# FPGA3.net
KiCad netlist of a schematic drawn in Altium Designer
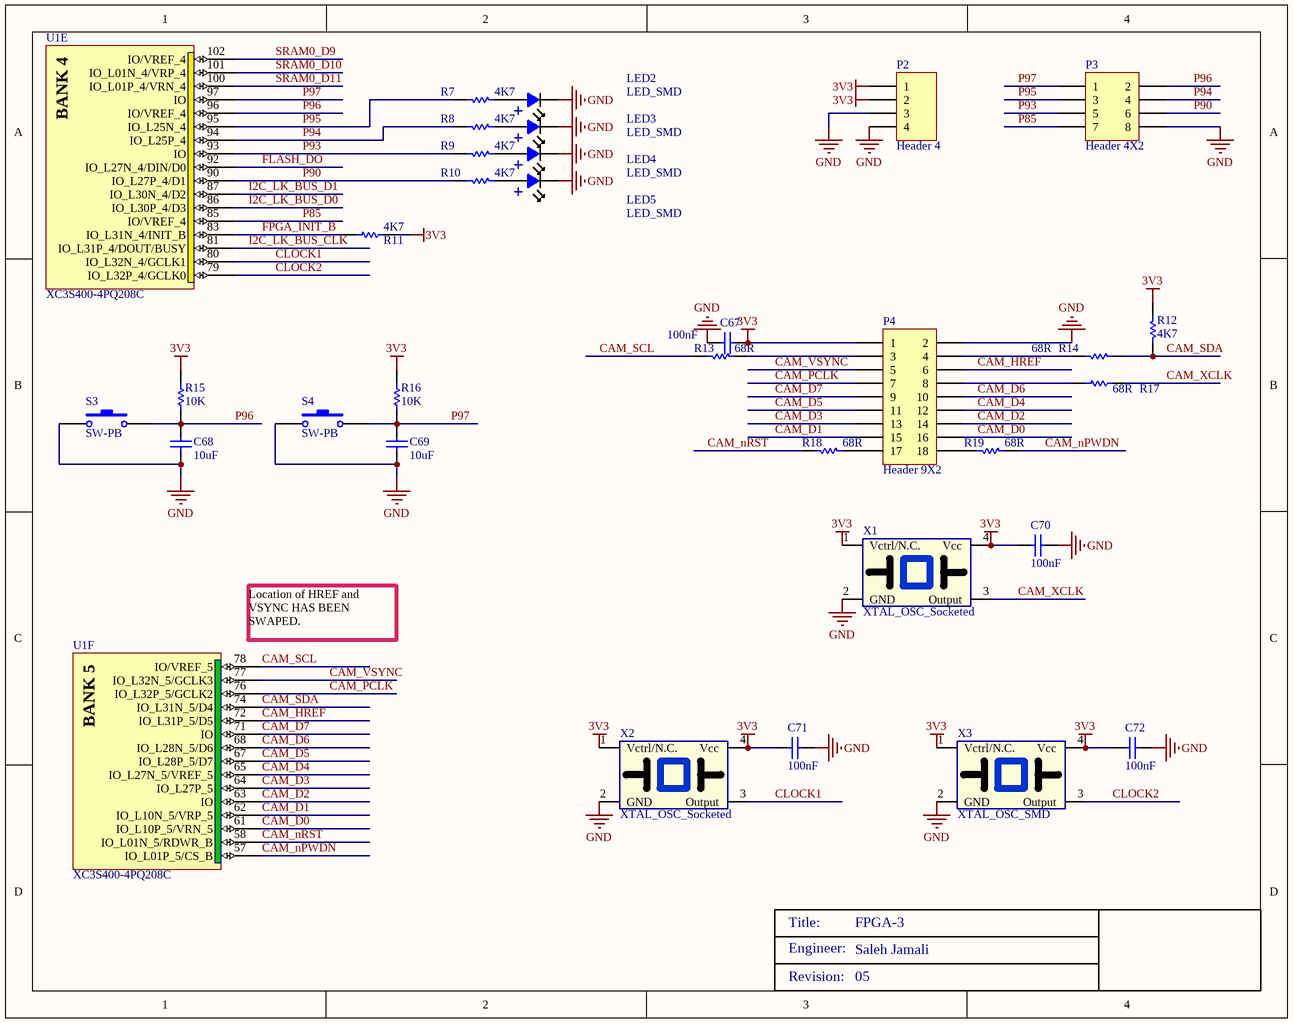
[diagram p0: FPGA3.SchDoc]

(export (version "E")
  (design (tool "Eeschema 10.0.6"))
  (components
    (comp (ref "C67")
      (value "100nF")
      (footprint "0805")
      (description "Ceramic Chip Capacitor - Standard")
      (fields (field (name "Comment") "C0805") (field (name "PUBLISHER") "Altium Limited"))
      (libsource (lib "KEMET Chip Capacitor") (part "C0805"))
    )
    (comp (ref "C68")
      (value "10uF")
      (footprint "0805")
      (description "Ceramic Chip Capacitor - Standard")
      (fields (field (name "Comment") "C0805") (field (name "PUBLISHER") "Altium Limited"))
      (libsource (lib "KEMET Chip Capacitor") (part "C0805"))
    )
    (comp (ref "C69")
      (value "10uF")
      (footprint "0805")
      (description "Ceramic Chip Capacitor - Standard")
      (fields (field (name "Comment") "C0805") (field (name "PUBLISHER") "Altium Limited"))
      (libsource (lib "KEMET Chip Capacitor") (part "C0805"))
    )
    (comp (ref "C70")
      (value "100nF")
      (footprint "0805")
      (description "Ceramic Chip Capacitor - Standard")
      (fields (field (name "Comment") "C0805") (field (name "PUBLISHER") "Altium Limited"))
      (libsource (lib "KEMET Chip Capacitor") (part "C0805"))
    )
    (comp (ref "C71")
      (value "100nF")
      (footprint "0805")
      (description "Ceramic Chip Capacitor - Standard")
      (fields (field (name "Comment") "C0805") (field (name "PUBLISHER") "Altium Limited"))
      (libsource (lib "KEMET Chip Capacitor") (part "C0805"))
    )
    (comp (ref "C72")
      (value "100nF")
      (footprint "0805")
      (description "Ceramic Chip Capacitor - Standard")
      (fields (field (name "Comment") "C0805") (field (name "PUBLISHER") "Altium Limited"))
      (libsource (lib "KEMET Chip Capacitor") (part "C0805"))
    )
    (comp (ref "LED2") (value "LED_SMD") (footprint "LED_805") (libsource (lib "LED_PRJCT") (part "LED_SMD")))
    (comp (ref "LED3") (value "LED_SMD") (footprint "LED_805") (libsource (lib "LED_PRJCT") (part "LED_SMD")))
    (comp (ref "LED4") (value "LED_SMD") (footprint "LED_805") (libsource (lib "LED_PRJCT") (part "LED_SMD")))
    (comp (ref "LED5") (value "LED_SMD") (footprint "LED_805") (libsource (lib "LED_PRJCT") (part "LED_SMD")))
    (comp (ref "P2")
      (value "Header 4")
      (footprint "HDR1X4")
      (description "Header, 4-Pin")
      (fields (field (name "PUBLISHER") "Altium Limited"))
      (libsource (lib "Miscellaneous Connectors") (part "Header 4"))
    )
    (comp (ref "P3")
      (value "Header 4X2")
      (footprint "HDR2X4")
      (description "Header, 4-Pin, Dual row")
      (fields (field (name "PUBLISHER") "Altium Limited"))
      (libsource (lib "Miscellaneous Connectors") (part "Header 4X2"))
    )
    (comp (ref "P4")
      (value "Header 9X2")
      (footprint "HDR2X9")
      (description "Header, 9-Pin, Dual row")
      (fields (field (name "PUBLISHER") "Altium Limited"))
      (libsource (lib "Miscellaneous Connectors") (part "Header 9X2"))
    )
    (comp (ref "R7")
      (value "4K7")
      (footprint "ERA-0805")
      (fields (field (name "PUBLISHER") "Altium Limited"))
      (libsource (lib "Panasonic Resistor") (part "ERA6Y"))
    )
    (comp (ref "R8")
      (value "4K7")
      (footprint "ERA-0805")
      (fields (field (name "PUBLISHER") "Altium Limited"))
      (libsource (lib "Panasonic Resistor") (part "ERA6Y"))
    )
    (comp (ref "R9")
      (value "4K7")
      (footprint "ERA-0805")
      (fields (field (name "PUBLISHER") "Altium Limited"))
      (libsource (lib "Panasonic Resistor") (part "ERA6Y"))
    )
    (comp (ref "R10")
      (value "4K7")
      (footprint "ERA-0805")
      (fields (field (name "PUBLISHER") "Altium Limited"))
      (libsource (lib "Panasonic Resistor") (part "ERA6Y"))
    )
    (comp (ref "R11")
      (value "4K7")
      (footprint "ERA-0805")
      (fields (field (name "PUBLISHER") "Altium Limited"))
      (libsource (lib "Panasonic Resistor") (part "ERA6Y"))
    )
    (comp (ref "R12")
      (value "4K7")
      (footprint "ERA-0805")
      (fields (field (name "PUBLISHER") "Altium Limited"))
      (libsource (lib "Panasonic Resistor") (part "ERA6Y"))
    )
    (comp (ref "R13")
      (value "68R")
      (footprint "ERA-0805")
      (fields (field (name "PUBLISHER") "Altium Limited"))
      (libsource (lib "Panasonic Resistor") (part "ERA6Y"))
    )
    (comp (ref "R14")
      (value "68R")
      (footprint "ERA-0805")
      (fields (field (name "PUBLISHER") "Altium Limited"))
      (libsource (lib "Panasonic Resistor") (part "ERA6Y"))
    )
    (comp (ref "R15")
      (value "10K")
      (footprint "ERA-0805")
      (fields (field (name "PUBLISHER") "Altium Limited"))
      (libsource (lib "Panasonic Resistor") (part "ERA6Y"))
    )
    (comp (ref "R16")
      (value "10K")
      (footprint "ERA-0805")
      (fields (field (name "PUBLISHER") "Altium Limited"))
      (libsource (lib "Panasonic Resistor") (part "ERA6Y"))
    )
    (comp (ref "R17")
      (value "68R")
      (footprint "ERA-0805")
      (fields (field (name "PUBLISHER") "Altium Limited"))
      (libsource (lib "Panasonic Resistor") (part "ERA6Y"))
    )
    (comp (ref "R18")
      (value "68R")
      (footprint "ERA-0805")
      (fields (field (name "PUBLISHER") "Altium Limited"))
      (libsource (lib "Panasonic Resistor") (part "ERA6Y"))
    )
    (comp (ref "R19")
      (value "68R")
      (footprint "ERA-0805")
      (fields (field (name "PUBLISHER") "Altium Limited"))
      (libsource (lib "Panasonic Resistor") (part "ERA6Y"))
    )
    (comp (ref "S3")
      (value "SW-PB")
      (footprint "SPST-2")
      (description "Switch")
      (fields (field (name "PUBLISHER") "Altium Limited"))
      (libsource (lib "Miscellaneous Devices") (part "SW-PB"))
    )
    (comp (ref "S4")
      (value "SW-PB")
      (footprint "SPST-2")
      (description "Switch")
      (fields (field (name "PUBLISHER") "Altium Limited"))
      (libsource (lib "Miscellaneous Devices") (part "SW-PB"))
    )
    (comp (ref "U1")
      (value "XC3S400-4PQ208C")
      (footprint "PQ208_N")
      (description "Spartan-3 1.2V FPGA, 141 User I/Os, 208-Pin PQFP, Standard Performance, Commercial Grade")
      (libsource (lib "Xilinx Spartan-3") (part "XC3S400-4PQ208C"))
    )
    (comp (ref "X1")
      (value "XTAL_OSC_Socketed")
      (footprint "CRYSTAL_OSC")
      (libsource (lib "CrystalOSC_prjct") (part "Crystal Oscillator"))
    )
    (comp (ref "X2")
      (value "XTAL_OSC_Socketed")
      (footprint "CRYSTAL_OSC")
      (libsource (lib "CrystalOSC_prjct") (part "Crystal Oscillator"))
    )
    (comp (ref "X3")
      (value "XTAL_OSC_SMD")
      (footprint "5x7mm SMD")
      (libsource (lib "CrystalOSC_prjct") (part "Crystal Oscillator"))
    )
  )
  (nets
    (net (code "1") (name "/CAM_D0") (class "Default")
      (node (ref "P4") (pin "16") (pinfunction "16_16") (pintype "passive"))
      (node (ref "U1") (pin "61") (pinfunction "IO_L10P_5/VRN_5_61") (pintype "bidirectional"))
    )
    (net (code "2") (name "/CAM_D1") (class "Default")
      (node (ref "P4") (pin "15") (pinfunction "15_15") (pintype "passive"))
      (node (ref "U1") (pin "62") (pinfunction "IO_L10N_5/VRP_5_62") (pintype "bidirectional"))
    )
    (net (code "3") (name "/CAM_D2") (class "Default")
      (node (ref "P4") (pin "14") (pinfunction "14_14") (pintype "passive"))
      (node (ref "U1") (pin "63") (pinfunction "IO_63") (pintype "bidirectional"))
    )
    (net (code "4") (name "/CAM_D3") (class "Default")
      (node (ref "P4") (pin "13") (pinfunction "13_13") (pintype "passive"))
      (node (ref "U1") (pin "64") (pinfunction "IO_L27P_5_64") (pintype "bidirectional"))
    )
    (net (code "5") (name "/CAM_D4") (class "Default")
      (node (ref "P4") (pin "12") (pinfunction "12_12") (pintype "passive"))
      (node (ref "U1") (pin "65") (pinfunction "IO_L27N_5/VREF_5_65") (pintype "bidirectional"))
    )
    (net (code "6") (name "/CAM_D5") (class "Default")
      (node (ref "P4") (pin "11") (pinfunction "11_11") (pintype "passive"))
      (node (ref "U1") (pin "67") (pinfunction "IO_L28P_5/D7_67") (pintype "bidirectional"))
    )
    (net (code "7") (name "/CAM_D6") (class "Default")
      (node (ref "P4") (pin "10") (pinfunction "10_10") (pintype "passive"))
      (node (ref "U1") (pin "68") (pinfunction "IO_L28N_5/D6_68") (pintype "bidirectional"))
    )
    (net (code "8") (name "/CAM_D7") (class "Default")
      (node (ref "P4") (pin "9") (pinfunction "9_9") (pintype "passive"))
      (node (ref "U1") (pin "71") (pinfunction "IO_71") (pintype "bidirectional"))
    )
    (net (code "9") (name "/CAM_HREF") (class "Default")
      (node (ref "P4") (pin "6") (pinfunction "6_6") (pintype "passive"))
      (node (ref "U1") (pin "72") (pinfunction "IO_L31P_5/D5_72") (pintype "bidirectional"))
    )
    (net (code "10") (name "/CAM_PCLK") (class "Default")
      (node (ref "P4") (pin "7") (pinfunction "7_7") (pintype "passive"))
      (node (ref "U1") (pin "76") (pinfunction "IO_L32P_5/GCLK2_76") (pintype "bidirectional"))
    )
    (net (code "11") (name "/CAM_SCL") (class "Default")
      (node (ref "R13") (pin "1") (pinfunction "1_1") (pintype "passive"))
      (node (ref "U1") (pin "78") (pinfunction "IO/VREF_5_78") (pintype "bidirectional"))
    )
    (net (code "12") (name "/CAM_SDA") (class "Default")
      (node (ref "R12") (pin "2") (pinfunction "2_2") (pintype "passive"))
      (node (ref "R14") (pin "1") (pinfunction "1_1") (pintype "passive"))
      (node (ref "U1") (pin "74") (pinfunction "IO_L31N_5/D4_74") (pintype "bidirectional"))
    )
    (net (code "13") (name "/CAM_VSYNC") (class "Default")
      (node (ref "P4") (pin "5") (pinfunction "5_5") (pintype "passive"))
      (node (ref "U1") (pin "77") (pinfunction "IO_L32N_5/GCLK3_77") (pintype "bidirectional"))
    )
    (net (code "14") (name "/CAM_XCLK") (class "Default")
      (node (ref "R17") (pin "1") (pinfunction "1_1") (pintype "passive"))
      (node (ref "X1") (pin "3") (pinfunction "Output_3") (pintype "passive"))
    )
    (net (code "15") (name "/CAM_nPWDN") (class "Default")
      (node (ref "R19") (pin "2") (pinfunction "2_2") (pintype "passive"))
      (node (ref "U1") (pin "57") (pinfunction "IO_L01P_5/CS_B_57") (pintype "bidirectional"))
    )
    (net (code "16") (name "/CAM_nRST") (class "Default")
      (node (ref "R18") (pin "1") (pinfunction "1_1") (pintype "passive"))
      (node (ref "U1") (pin "58") (pinfunction "IO_L01N_5/RDWR_B_58") (pintype "bidirectional"))
    )
    (net (code "17") (name "/CLOCK1") (class "Default")
      (node (ref "U1") (pin "80") (pinfunction "IO_L32N_4/GCLK1_80") (pintype "bidirectional"))
      (node (ref "X2") (pin "3") (pinfunction "Output_3") (pintype "passive"))
    )
    (net (code "18") (name "/CLOCK2") (class "Default")
      (node (ref "U1") (pin "79") (pinfunction "IO_L32P_4/GCLK0_79") (pintype "bidirectional"))
      (node (ref "X3") (pin "3") (pinfunction "Output_3") (pintype "passive"))
    )
    (net (code "19") (name "/FLASH_DO") (class "Default")
      (node (ref "U1") (pin "92") (pinfunction "IO_L27N_4/DIN/D0_92") (pintype "bidirectional"))
    )
    (net (code "20") (name "/FPGA_INIT_B") (class "Default")
      (node (ref "R11") (pin "2") (pinfunction "2_2") (pintype "passive"))
      (node (ref "U1") (pin "83") (pinfunction "IO_L31N_4/INIT_B_83") (pintype "bidirectional"))
    )
    (net (code "21") (name "/I2C_LK_BUS_CLK") (class "Default")
      (node (ref "U1") (pin "81") (pinfunction "IO_L31P_4/DOUT/BUSY_81") (pintype "bidirectional"))
    )
    (net (code "22") (name "/I2C_LK_BUS_D0") (class "Default")
      (node (ref "U1") (pin "86") (pinfunction "IO_L30P_4/D3_86") (pintype "bidirectional"))
    )
    (net (code "23") (name "/I2C_LK_BUS_D1") (class "Default")
      (node (ref "U1") (pin "87") (pinfunction "IO_L30N_4/D2_87") (pintype "bidirectional"))
    )
    (net (code "24") (name "/P85") (class "Default")
      (node (ref "P3") (pin "7") (pinfunction "7_7") (pintype "passive"))
      (node (ref "U1") (pin "85") (pinfunction "IO/VREF_4_85") (pintype "bidirectional"))
    )
    (net (code "25") (name "/P90") (class "Default")
      (node (ref "P3") (pin "6") (pinfunction "6_6") (pintype "passive"))
      (node (ref "R10") (pin "1") (pinfunction "1_1") (pintype "passive"))
      (node (ref "U1") (pin "90") (pinfunction "IO_L27P_4/D1_90") (pintype "bidirectional"))
    )
    (net (code "26") (name "/P93") (class "Default")
      (node (ref "P3") (pin "5") (pinfunction "5_5") (pintype "passive"))
      (node (ref "R9") (pin "1") (pinfunction "1_1") (pintype "passive"))
      (node (ref "U1") (pin "93") (pinfunction "IO_93") (pintype "bidirectional"))
    )
    (net (code "27") (name "/P94") (class "Default")
      (node (ref "P3") (pin "4") (pinfunction "4_4") (pintype "passive"))
      (node (ref "R8") (pin "1") (pinfunction "1_1") (pintype "passive"))
      (node (ref "U1") (pin "94") (pinfunction "IO_L25P_4_94") (pintype "bidirectional"))
    )
    (net (code "28") (name "/P95") (class "Default")
      (node (ref "P3") (pin "3") (pinfunction "3_3") (pintype "passive"))
      (node (ref "R7") (pin "1") (pinfunction "1_1") (pintype "passive"))
      (node (ref "U1") (pin "95") (pinfunction "IO_L25N_4_95") (pintype "bidirectional"))
    )
    (net (code "29") (name "/P96") (class "Default")
      (node (ref "C68") (pin "2") (pinfunction "2_2") (pintype "passive"))
      (node (ref "P3") (pin "2") (pinfunction "2_2") (pintype "passive"))
      (node (ref "R15") (pin "2") (pinfunction "2_2") (pintype "passive"))
      (node (ref "S3") (pin "2") (pinfunction "2_2") (pintype "passive"))
      (node (ref "U1") (pin "96") (pinfunction "IO/VREF_4_96") (pintype "bidirectional"))
    )
    (net (code "30") (name "/P97") (class "Default")
      (node (ref "C69") (pin "2") (pinfunction "2_2") (pintype "passive"))
      (node (ref "P3") (pin "1") (pinfunction "1_1") (pintype "passive"))
      (node (ref "R16") (pin "2") (pinfunction "2_2") (pintype "passive"))
      (node (ref "S4") (pin "2") (pinfunction "2_2") (pintype "passive"))
      (node (ref "U1") (pin "97") (pinfunction "IO_97") (pintype "bidirectional"))
    )
    (net (code "31") (name "/SRAM0_D9") (class "Default")
      (node (ref "U1") (pin "102") (pinfunction "IO/VREF_4_102") (pintype "bidirectional"))
    )
    (net (code "32") (name "/SRAM0_D10") (class "Default")
      (node (ref "U1") (pin "101") (pinfunction "IO_L01N_4/VRP_4_101") (pintype "bidirectional"))
    )
    (net (code "33") (name "/SRAM0_D11") (class "Default")
      (node (ref "U1") (pin "100") (pinfunction "IO_L01P_4/VRN_4_100") (pintype "bidirectional"))
    )
    (net (code "34") (name "3V3") (class "Default")
      (node (ref "C67") (pin "2") (pinfunction "2_2") (pintype "passive"))
      (node (ref "C70") (pin "1") (pinfunction "1_1") (pintype "passive"))
      (node (ref "C71") (pin "1") (pinfunction "1_1") (pintype "passive"))
      (node (ref "C72") (pin "1") (pinfunction "1_1") (pintype "passive"))
      (node (ref "P2") (pin "1") (pinfunction "1_1") (pintype "passive"))
      (node (ref "P2") (pin "2") (pinfunction "2_2") (pintype "passive"))
      (node (ref "P4") (pin "1") (pinfunction "1_1") (pintype "passive"))
      (node (ref "R11") (pin "1") (pinfunction "1_1") (pintype "passive"))
      (node (ref "R12") (pin "1") (pinfunction "1_1") (pintype "passive"))
      (node (ref "R15") (pin "1") (pinfunction "1_1") (pintype "passive"))
      (node (ref "R16") (pin "1") (pinfunction "1_1") (pintype "passive"))
      (node (ref "X1") (pin "1") (pinfunction "Vctrl/N.C._1") (pintype "passive"))
      (node (ref "X1") (pin "4") (pinfunction "Vcc_4") (pintype "passive"))
      (node (ref "X2") (pin "1") (pinfunction "Vctrl/N.C._1") (pintype "passive"))
      (node (ref "X2") (pin "4") (pinfunction "Vcc_4") (pintype "passive"))
      (node (ref "X3") (pin "1") (pinfunction "Vctrl/N.C._1") (pintype "passive"))
      (node (ref "X3") (pin "4") (pinfunction "Vcc_4") (pintype "passive"))
    )
    (net (code "35") (name "GND") (class "Default")
      (node (ref "C67") (pin "1") (pinfunction "1_1") (pintype "passive"))
      (node (ref "C68") (pin "1") (pinfunction "1_1") (pintype "passive"))
      (node (ref "C69") (pin "1") (pinfunction "1_1") (pintype "passive"))
      (node (ref "C70") (pin "2") (pinfunction "2_2") (pintype "passive"))
      (node (ref "C71") (pin "2") (pinfunction "2_2") (pintype "passive"))
      (node (ref "C72") (pin "2") (pinfunction "2_2") (pintype "passive"))
      (node (ref "LED2") (pin "2") (pinfunction "2_2") (pintype "passive"))
      (node (ref "LED3") (pin "2") (pinfunction "2_2") (pintype "passive"))
      (node (ref "LED4") (pin "2") (pinfunction "2_2") (pintype "passive"))
      (node (ref "LED5") (pin "2") (pinfunction "2_2") (pintype "passive"))
      (node (ref "P2") (pin "3") (pinfunction "3_3") (pintype "passive"))
      (node (ref "P2") (pin "4") (pinfunction "4_4") (pintype "passive"))
      (node (ref "P3") (pin "8") (pinfunction "8_8") (pintype "passive"))
      (node (ref "P4") (pin "2") (pinfunction "2_2") (pintype "passive"))
      (node (ref "S3") (pin "1") (pinfunction "1_1") (pintype "passive"))
      (node (ref "S4") (pin "1") (pinfunction "1_1") (pintype "passive"))
      (node (ref "X1") (pin "2") (pinfunction "GND_2") (pintype "passive"))
      (node (ref "X2") (pin "2") (pinfunction "GND_2") (pintype "passive"))
      (node (ref "X3") (pin "2") (pinfunction "GND_2") (pintype "passive"))
    )
    (net (code "36") (name "Net-(LED2-Pad1)") (class "Default")
      (node (ref "LED2") (pin "1") (pinfunction "1_1") (pintype "passive"))
      (node (ref "R7") (pin "2") (pinfunction "2_2") (pintype "passive"))
    )
    (net (code "37") (name "Net-(LED3-Pad1)") (class "Default")
      (node (ref "LED3") (pin "1") (pinfunction "1_1") (pintype "passive"))
      (node (ref "R8") (pin "2") (pinfunction "2_2") (pintype "passive"))
    )
    (net (code "38") (name "Net-(LED4-Pad1)") (class "Default")
      (node (ref "LED4") (pin "1") (pinfunction "1_1") (pintype "passive"))
      (node (ref "R9") (pin "2") (pinfunction "2_2") (pintype "passive"))
    )
    (net (code "39") (name "Net-(LED5-Pad1)") (class "Default")
      (node (ref "LED5") (pin "1") (pinfunction "1_1") (pintype "passive"))
      (node (ref "R10") (pin "2") (pinfunction "2_2") (pintype "passive"))
    )
    (net (code "40") (name "Net-(P4-Pad3)") (class "Default")
      (node (ref "P4") (pin "3") (pinfunction "3_3") (pintype "passive"))
      (node (ref "R13") (pin "2") (pinfunction "2_2") (pintype "passive"))
    )
    (net (code "41") (name "Net-(P4-Pad4)") (class "Default")
      (node (ref "P4") (pin "4") (pinfunction "4_4") (pintype "passive"))
      (node (ref "R14") (pin "2") (pinfunction "2_2") (pintype "passive"))
    )
    (net (code "42") (name "Net-(P4-Pad8)") (class "Default")
      (node (ref "P4") (pin "8") (pinfunction "8_8") (pintype "passive"))
      (node (ref "R17") (pin "2") (pinfunction "2_2") (pintype "passive"))
    )
    (net (code "43") (name "Net-(P4-Pad17)") (class "Default")
      (node (ref "P4") (pin "17") (pinfunction "17_17") (pintype "passive"))
      (node (ref "R18") (pin "2") (pinfunction "2_2") (pintype "passive"))
    )
    (net (code "44") (name "Net-(P4-Pad18)") (class "Default")
      (node (ref "P4") (pin "18") (pinfunction "18_18") (pintype "passive"))
      (node (ref "R19") (pin "1") (pinfunction "1_1") (pintype "passive"))
    )
  )
)
